# SCH_LatencyMeter_Loc1_2024-01-18.net
KiCad netlist of a schematic drawn in EasyEDA
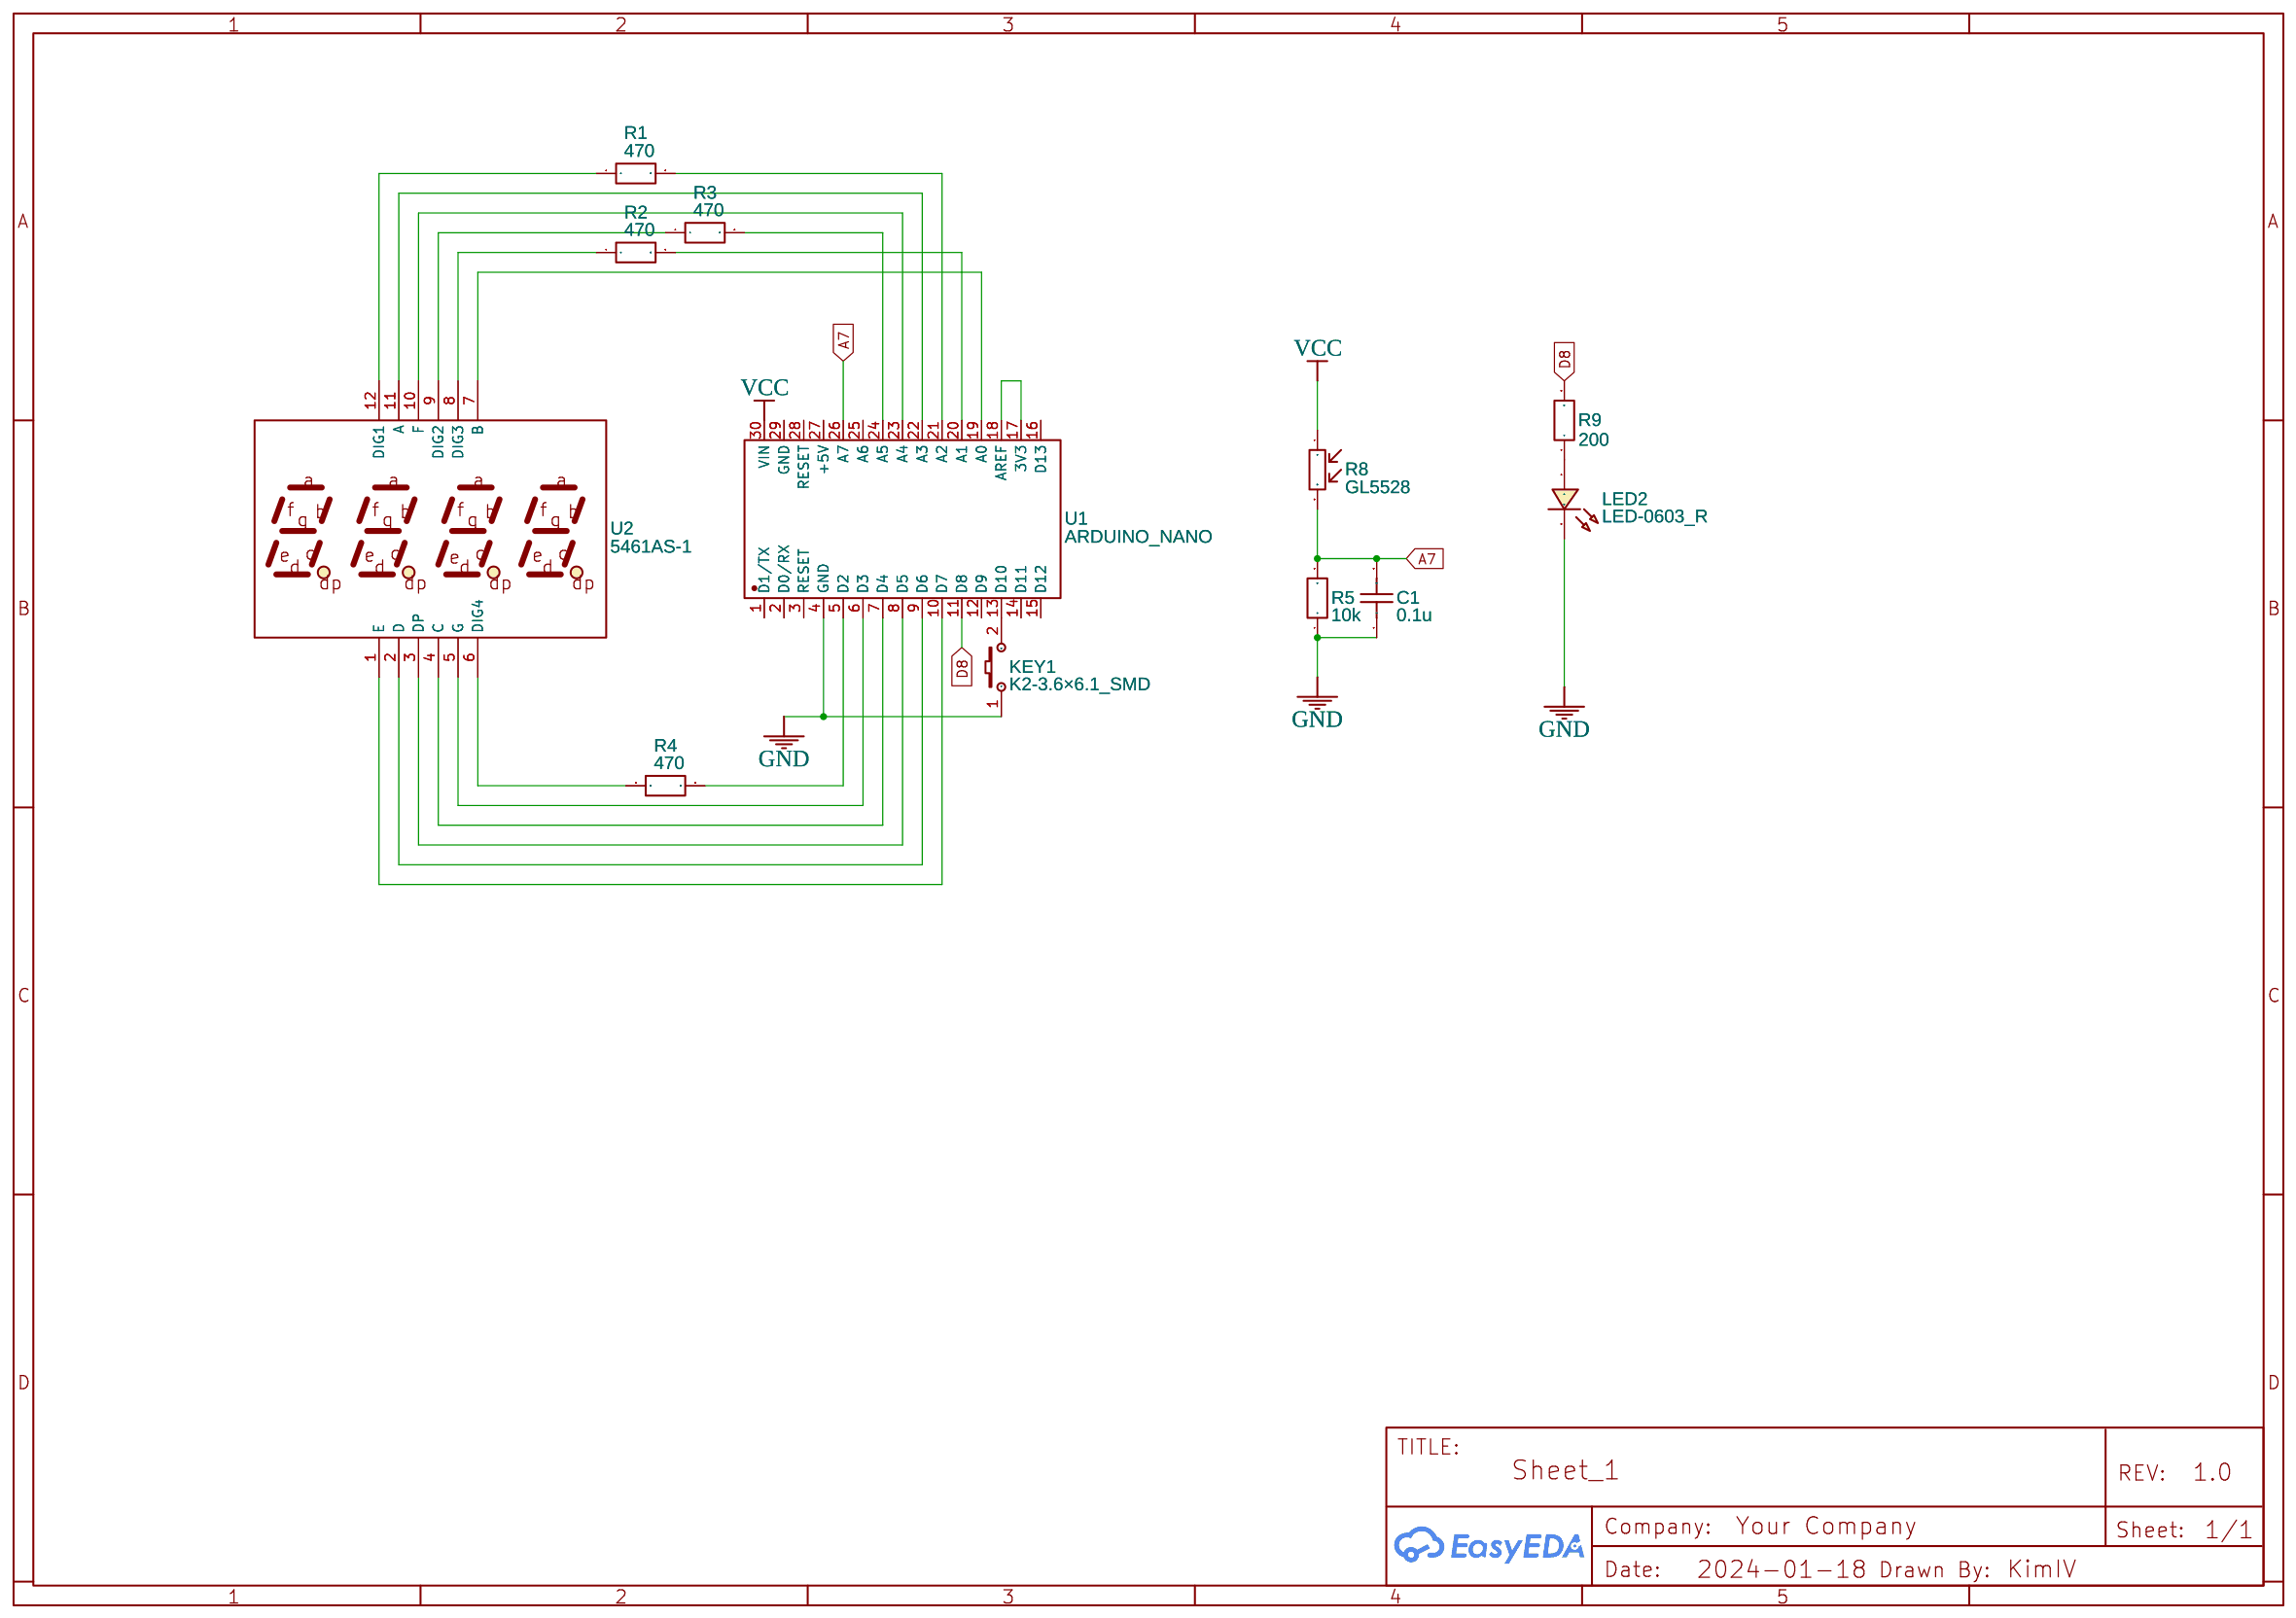
[diagram p0: schematic sheet]

(export (version "E")
  (design (tool "Eeschema 10.0.6"))
  (components
    (comp (ref "C1") (value "0.1u") (libsource (lib "") (part "C_0603_US")))
    (comp (ref "KEY1")
      (value "K2-3.6×6.1_SMD")
      (fields (field (name "Manufacturer Part") "K2-1107ST-A4SW-06"))
      (libsource (lib "") (part "K2-3.6×6.1_SMD"))
    )
    (comp (ref "LED2")
      (value "LED-0603_R")
      (fields
        (field (name "Manufacturer Part") "19-217/R6C-AL1M2VY/3T")
        (field (name "Manufacturer") "EVERLIGHT(台湾亿光)")
      )
      (libsource (lib "") (part "LED-0603_R"))
    )
    (comp (ref "R1") (value "470") (libsource (lib "") (part "R_0603_EU")))
    (comp (ref "R2") (value "470") (libsource (lib "") (part "R_0603_EU")))
    (comp (ref "R3") (value "470") (libsource (lib "") (part "R_0603_EU")))
    (comp (ref "R4") (value "470") (libsource (lib "") (part "R_0603_EU")))
    (comp (ref "R5") (value "10k") (libsource (lib "") (part "R_0603_EU_1")))
    (comp (ref "R8")
      (value "GL5528")
      (fields (field (name "Manufacturer") "森霸"))
      (libsource (lib "") (part "GL5528"))
    )
    (comp (ref "R9") (value "200") (libsource (lib "") (part "R_0603_EU_1")))
    (comp (ref "U1") (value "ARDUINO_NANO") (libsource (lib "") (part "ARDUINO_NANO")))
    (comp (ref "U2") (value "5461AS-1") (libsource (lib "") (part "5461AS-1")))
  )
  (nets
    (net (code "1") (name "A7") (class "Default")
      (node (ref "C1") (pin "2") (pinfunction "2_2") (pintype "unspecified"))
      (node (ref "R5") (pin "2") (pinfunction "2_2") (pintype "unspecified"))
      (node (ref "R8") (pin "2") (pinfunction "2_2") (pintype "input"))
      (node (ref "U1") (pin "26") (pinfunction "A7_26") (pintype "unspecified"))
    )
    (net (code "2") (name "D8") (class "Default")
      (node (ref "R9") (pin "2") (pinfunction "2_2") (pintype "unspecified"))
      (node (ref "U1") (pin "11") (pinfunction "D8_11") (pintype "unspecified"))
    )
    (net (code "3") (name "GND") (class "Default")
      (node (ref "C1") (pin "1") (pinfunction "1_1") (pintype "unspecified"))
      (node (ref "KEY1") (pin "1") (pinfunction "1_1") (pintype "unspecified"))
      (node (ref "LED2") (pin "2") (pinfunction "2_2") (pintype "unspecified"))
      (node (ref "R5") (pin "1") (pinfunction "1_1") (pintype "unspecified"))
      (node (ref "U1") (pin "4") (pinfunction "GND_4") (pintype "unspecified"))
    )
    (net (code "4") (name "Net-(LED2-Pad1)") (class "Default")
      (node (ref "LED2") (pin "1") (pinfunction "1_1") (pintype "unspecified"))
      (node (ref "R9") (pin "1") (pinfunction "1_1") (pintype "unspecified"))
    )
    (net (code "5") (name "Net-(U1-3V3)") (class "Default")
      (node (ref "U1") (pin "17") (pinfunction "3V3_17") (pintype "unspecified"))
      (node (ref "U1") (pin "18") (pinfunction "AREF_18") (pintype "unspecified"))
    )
    (net (code "6") (name "Net-(U1-A0)") (class "Default")
      (node (ref "U1") (pin "19") (pinfunction "A0_19") (pintype "unspecified"))
      (node (ref "U2") (pin "7") (pinfunction "B_7") (pintype "input"))
    )
    (net (code "7") (name "Net-(U1-A1)") (class "Default")
      (node (ref "R2") (pin "2") (pinfunction "2_2") (pintype "unspecified"))
      (node (ref "U1") (pin "20") (pinfunction "A1_20") (pintype "unspecified"))
    )
    (net (code "8") (name "Net-(U1-A2)") (class "Default")
      (node (ref "R1") (pin "2") (pinfunction "2_2") (pintype "unspecified"))
      (node (ref "U1") (pin "21") (pinfunction "A2_21") (pintype "unspecified"))
    )
    (net (code "9") (name "Net-(U1-A3)") (class "Default")
      (node (ref "U1") (pin "22") (pinfunction "A3_22") (pintype "unspecified"))
      (node (ref "U2") (pin "11") (pinfunction "A_11") (pintype "input"))
    )
    (net (code "10") (name "Net-(U1-A4)") (class "Default")
      (node (ref "U1") (pin "23") (pinfunction "A4_23") (pintype "unspecified"))
      (node (ref "U2") (pin "10") (pinfunction "F_10") (pintype "input"))
    )
    (net (code "11") (name "Net-(U1-A5)") (class "Default")
      (node (ref "R3") (pin "2") (pinfunction "2_2") (pintype "unspecified"))
      (node (ref "U1") (pin "24") (pinfunction "A5_24") (pintype "unspecified"))
    )
    (net (code "12") (name "Net-(U1-D2)") (class "Default")
      (node (ref "R4") (pin "2") (pinfunction "2_2") (pintype "unspecified"))
      (node (ref "U1") (pin "5") (pinfunction "D2_5") (pintype "unspecified"))
    )
    (net (code "13") (name "Net-(U1-D3)") (class "Default")
      (node (ref "U1") (pin "6") (pinfunction "D3_6") (pintype "unspecified"))
      (node (ref "U2") (pin "5") (pinfunction "G_5") (pintype "input"))
    )
    (net (code "14") (name "Net-(U1-D4)") (class "Default")
      (node (ref "U1") (pin "7") (pinfunction "D4_7") (pintype "unspecified"))
      (node (ref "U2") (pin "4") (pinfunction "C_4") (pintype "input"))
    )
    (net (code "15") (name "Net-(U1-D5)") (class "Default")
      (node (ref "U1") (pin "8") (pinfunction "D5_8") (pintype "unspecified"))
      (node (ref "U2") (pin "3") (pinfunction "DP_3") (pintype "input"))
    )
    (net (code "16") (name "Net-(U1-D6)") (class "Default")
      (node (ref "U1") (pin "9") (pinfunction "D6_9") (pintype "unspecified"))
      (node (ref "U2") (pin "2") (pinfunction "D_2") (pintype "input"))
    )
    (net (code "17") (name "Net-(U1-D7)") (class "Default")
      (node (ref "U1") (pin "10") (pinfunction "D7_10") (pintype "unspecified"))
      (node (ref "U2") (pin "1") (pinfunction "E_1") (pintype "input"))
    )
    (net (code "18") (name "Net-(U1-D10)") (class "Default")
      (node (ref "KEY1") (pin "2") (pinfunction "2_2") (pintype "unspecified"))
      (node (ref "U1") (pin "13") (pinfunction "D10_13") (pintype "unspecified"))
    )
    (net (code "19") (name "Net-(U2-DIG1)") (class "Default")
      (node (ref "R1") (pin "1") (pinfunction "1_1") (pintype "unspecified"))
      (node (ref "U2") (pin "12") (pinfunction "DIG1_12") (pintype "input"))
    )
    (net (code "20") (name "Net-(U2-DIG2)") (class "Default")
      (node (ref "R3") (pin "1") (pinfunction "1_1") (pintype "unspecified"))
      (node (ref "U2") (pin "9") (pinfunction "DIG2_9") (pintype "input"))
    )
    (net (code "21") (name "Net-(U2-DIG3)") (class "Default")
      (node (ref "R2") (pin "1") (pinfunction "1_1") (pintype "unspecified"))
      (node (ref "U2") (pin "8") (pinfunction "DIG3_8") (pintype "input"))
    )
    (net (code "22") (name "Net-(U2-DIG4)") (class "Default")
      (node (ref "R4") (pin "1") (pinfunction "1_1") (pintype "unspecified"))
      (node (ref "U2") (pin "6") (pinfunction "DIG4_6") (pintype "input"))
    )
    (net (code "23") (name "VCC") (class "Default")
      (node (ref "R8") (pin "1") (pinfunction "1_1") (pintype "input"))
      (node (ref "U1") (pin "30") (pinfunction "VIN_30") (pintype "unspecified"))
    )
    (net (code "24") (name "unconnected-(U1-+5V-Pad27)") (class "Default")
      (node (ref "U1") (pin "27") (pinfunction "+5V_27") (pintype "unspecified"))
    )
    (net (code "25") (name "unconnected-(U1-A6-Pad25)") (class "Default")
      (node (ref "U1") (pin "25") (pinfunction "A6_25") (pintype "unspecified"))
    )
    (net (code "26") (name "unconnected-(U1-D0{slash}RX-Pad2)") (class "Default")
      (node (ref "U1") (pin "2") (pinfunction "D0/RX_2") (pintype "unspecified"))
    )
    (net (code "27") (name "unconnected-(U1-D1{slash}TX-Pad1)") (class "Default")
      (node (ref "U1") (pin "1") (pinfunction "D1/TX_1") (pintype "unspecified"))
    )
    (net (code "28") (name "unconnected-(U1-D9-Pad12)") (class "Default")
      (node (ref "U1") (pin "12") (pinfunction "D9_12") (pintype "unspecified"))
    )
    (net (code "29") (name "unconnected-(U1-D11-Pad14)") (class "Default")
      (node (ref "U1") (pin "14") (pinfunction "D11_14") (pintype "unspecified"))
    )
    (net (code "30") (name "unconnected-(U1-D12-Pad15)") (class "Default")
      (node (ref "U1") (pin "15") (pinfunction "D12_15") (pintype "unspecified"))
    )
    (net (code "31") (name "unconnected-(U1-D13-Pad16)") (class "Default")
      (node (ref "U1") (pin "16") (pinfunction "D13_16") (pintype "unspecified"))
    )
    (net (code "32") (name "unconnected-(U1-GND-Pad29)") (class "Default")
      (node (ref "U1") (pin "29") (pinfunction "GND_29") (pintype "unspecified"))
    )
    (net (code "33") (name "unconnected-(U1-RESET-Pad3)") (class "Default")
      (node (ref "U1") (pin "3") (pinfunction "RESET_3") (pintype "unspecified"))
    )
    (net (code "34") (name "unconnected-(U1-RESET-Pad28)") (class "Default")
      (node (ref "U1") (pin "28") (pinfunction "RESET_28") (pintype "unspecified"))
    )
  )
)
